# cBlocks_proto_shield.net
KiCad netlist of a schematic drawn in EAGLE
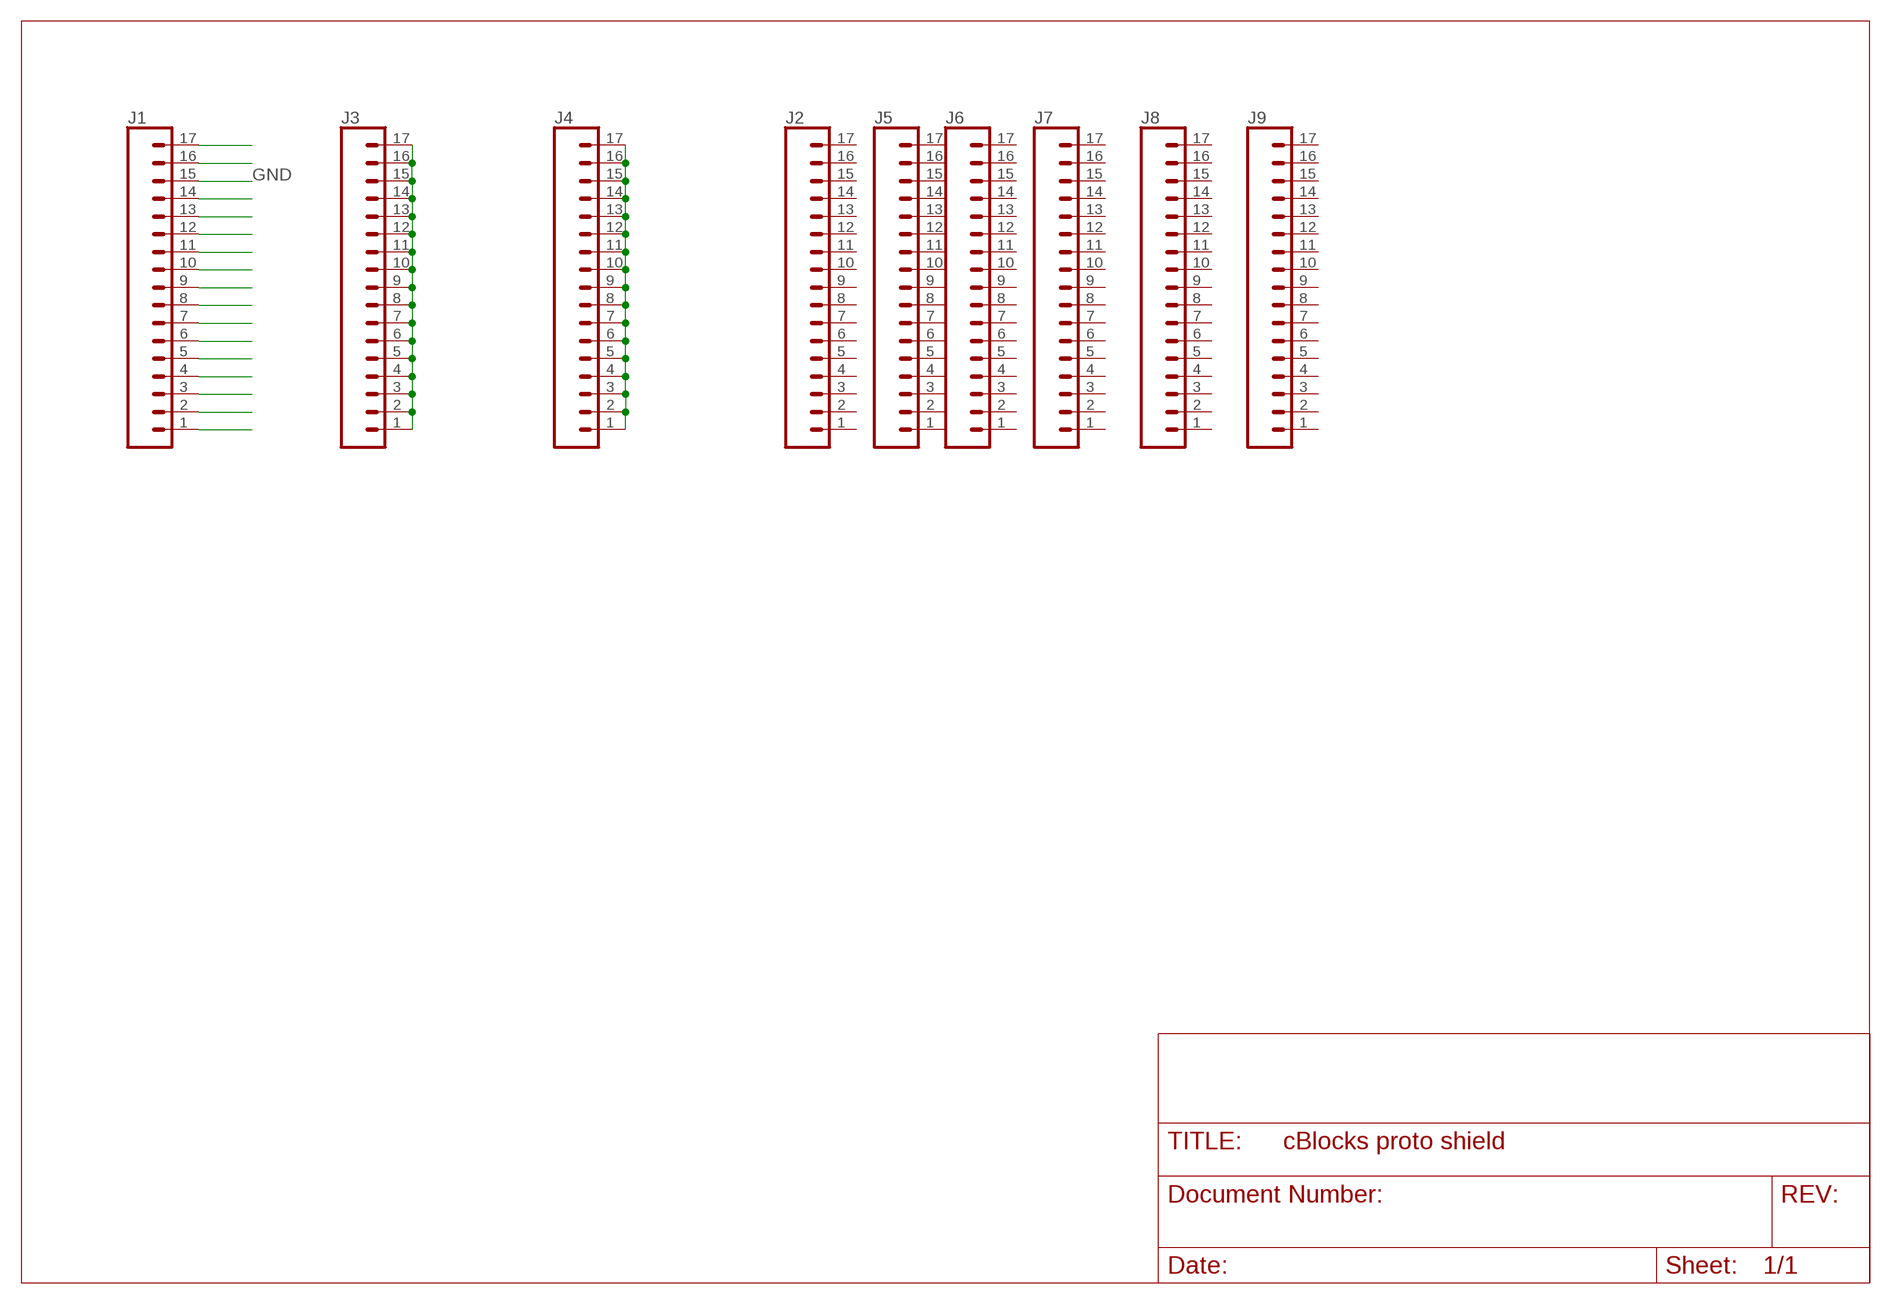
[diagram p0: schematic, sheet 1]

(export (version "E")
  (design (tool "Eeschema 10.0.6"))
  (components
    (comp (ref "J1")
      (value "CONN_17NOSILK")
      (footprint "eagle-import:1X17_NO_SILK")
      (libsource (lib "eagle-import") (part "CONN_17NOSILK"))
    )
    (comp (ref "J2")
      (value "CONN_17NOSILK")
      (footprint "eagle-import:1X17_NO_SILK")
      (libsource (lib "eagle-import") (part "CONN_17NOSILK"))
    )
    (comp (ref "J3")
      (value "CONN_17NOSILK")
      (footprint "eagle-import:1X17_NO_SILK")
      (libsource (lib "eagle-import") (part "CONN_17NOSILK"))
    )
    (comp (ref "J4")
      (value "CONN_17NOSILK")
      (footprint "eagle-import:1X17_NO_SILK")
      (libsource (lib "eagle-import") (part "CONN_17NOSILK"))
    )
    (comp (ref "J5")
      (value "CONN_17NOSILK")
      (footprint "eagle-import:1X17_NO_SILK")
      (libsource (lib "eagle-import") (part "CONN_17NOSILK"))
    )
    (comp (ref "J6")
      (value "CONN_17NOSILK")
      (footprint "eagle-import:1X17_NO_SILK")
      (libsource (lib "eagle-import") (part "CONN_17NOSILK"))
    )
    (comp (ref "J7")
      (value "CONN_17NOSILK")
      (footprint "eagle-import:1X17_NO_SILK")
      (libsource (lib "eagle-import") (part "CONN_17NOSILK"))
    )
    (comp (ref "J8")
      (value "CONN_17NOSILK")
      (footprint "eagle-import:1X17_NO_SILK")
      (libsource (lib "eagle-import") (part "CONN_17NOSILK"))
    )
    (comp (ref "J9")
      (value "CONN_17NOSILK")
      (footprint "eagle-import:1X17_NO_SILK")
      (libsource (lib "eagle-import") (part "CONN_17NOSILK"))
    )
  )
  (nets
    (net (code "1") (name "/GND") (class "Default")
      (node (ref "J1") (pin "15") (pinfunction "15_15") (pintype "passive"))
    )
    (net (code "2") (name "Net-(J3-Pad1)") (class "Default")
      (node (ref "J3") (pin "1") (pinfunction "1_1") (pintype "passive"))
      (node (ref "J3") (pin "10") (pinfunction "10_10") (pintype "passive"))
      (node (ref "J3") (pin "11") (pinfunction "11_11") (pintype "passive"))
      (node (ref "J3") (pin "12") (pinfunction "12_12") (pintype "passive"))
      (node (ref "J3") (pin "13") (pinfunction "13_13") (pintype "passive"))
      (node (ref "J3") (pin "14") (pinfunction "14_14") (pintype "passive"))
      (node (ref "J3") (pin "15") (pinfunction "15_15") (pintype "passive"))
      (node (ref "J3") (pin "16") (pinfunction "16_16") (pintype "passive"))
      (node (ref "J3") (pin "17") (pinfunction "17_17") (pintype "passive"))
      (node (ref "J3") (pin "2") (pinfunction "2_2") (pintype "passive"))
      (node (ref "J3") (pin "3") (pinfunction "3_3") (pintype "passive"))
      (node (ref "J3") (pin "4") (pinfunction "4_4") (pintype "passive"))
      (node (ref "J3") (pin "5") (pinfunction "5_5") (pintype "passive"))
      (node (ref "J3") (pin "6") (pinfunction "6_6") (pintype "passive"))
      (node (ref "J3") (pin "7") (pinfunction "7_7") (pintype "passive"))
      (node (ref "J3") (pin "8") (pinfunction "8_8") (pintype "passive"))
      (node (ref "J3") (pin "9") (pinfunction "9_9") (pintype "passive"))
    )
    (net (code "3") (name "Net-(J4-Pad1)") (class "Default")
      (node (ref "J4") (pin "1") (pinfunction "1_1") (pintype "passive"))
      (node (ref "J4") (pin "10") (pinfunction "10_10") (pintype "passive"))
      (node (ref "J4") (pin "11") (pinfunction "11_11") (pintype "passive"))
      (node (ref "J4") (pin "12") (pinfunction "12_12") (pintype "passive"))
      (node (ref "J4") (pin "13") (pinfunction "13_13") (pintype "passive"))
      (node (ref "J4") (pin "14") (pinfunction "14_14") (pintype "passive"))
      (node (ref "J4") (pin "15") (pinfunction "15_15") (pintype "passive"))
      (node (ref "J4") (pin "16") (pinfunction "16_16") (pintype "passive"))
      (node (ref "J4") (pin "17") (pinfunction "17_17") (pintype "passive"))
      (node (ref "J4") (pin "2") (pinfunction "2_2") (pintype "passive"))
      (node (ref "J4") (pin "3") (pinfunction "3_3") (pintype "passive"))
      (node (ref "J4") (pin "4") (pinfunction "4_4") (pintype "passive"))
      (node (ref "J4") (pin "5") (pinfunction "5_5") (pintype "passive"))
      (node (ref "J4") (pin "6") (pinfunction "6_6") (pintype "passive"))
      (node (ref "J4") (pin "7") (pinfunction "7_7") (pintype "passive"))
      (node (ref "J4") (pin "8") (pinfunction "8_8") (pintype "passive"))
      (node (ref "J4") (pin "9") (pinfunction "9_9") (pintype "passive"))
    )
    (net (code "4") (name "unconnected-(J1-Pad1)") (class "Default")
      (node (ref "J1") (pin "1") (pinfunction "1_1") (pintype "passive"))
    )
    (net (code "5") (name "unconnected-(J1-Pad2)") (class "Default")
      (node (ref "J1") (pin "2") (pinfunction "2_2") (pintype "passive"))
    )
    (net (code "6") (name "unconnected-(J1-Pad3)") (class "Default")
      (node (ref "J1") (pin "3") (pinfunction "3_3") (pintype "passive"))
    )
    (net (code "7") (name "unconnected-(J1-Pad4)") (class "Default")
      (node (ref "J1") (pin "4") (pinfunction "4_4") (pintype "passive"))
    )
    (net (code "8") (name "unconnected-(J1-Pad5)") (class "Default")
      (node (ref "J1") (pin "5") (pinfunction "5_5") (pintype "passive"))
    )
    (net (code "9") (name "unconnected-(J1-Pad6)") (class "Default")
      (node (ref "J1") (pin "6") (pinfunction "6_6") (pintype "passive"))
    )
    (net (code "10") (name "unconnected-(J1-Pad7)") (class "Default")
      (node (ref "J1") (pin "7") (pinfunction "7_7") (pintype "passive"))
    )
    (net (code "11") (name "unconnected-(J1-Pad8)") (class "Default")
      (node (ref "J1") (pin "8") (pinfunction "8_8") (pintype "passive"))
    )
    (net (code "12") (name "unconnected-(J1-Pad9)") (class "Default")
      (node (ref "J1") (pin "9") (pinfunction "9_9") (pintype "passive"))
    )
    (net (code "13") (name "unconnected-(J1-Pad10)") (class "Default")
      (node (ref "J1") (pin "10") (pinfunction "10_10") (pintype "passive"))
    )
    (net (code "14") (name "unconnected-(J1-Pad11)") (class "Default")
      (node (ref "J1") (pin "11") (pinfunction "11_11") (pintype "passive"))
    )
    (net (code "15") (name "unconnected-(J1-Pad12)") (class "Default")
      (node (ref "J1") (pin "12") (pinfunction "12_12") (pintype "passive"))
    )
    (net (code "16") (name "unconnected-(J1-Pad13)") (class "Default")
      (node (ref "J1") (pin "13") (pinfunction "13_13") (pintype "passive"))
    )
    (net (code "17") (name "unconnected-(J1-Pad14)") (class "Default")
      (node (ref "J1") (pin "14") (pinfunction "14_14") (pintype "passive"))
    )
    (net (code "18") (name "unconnected-(J1-Pad16)") (class "Default")
      (node (ref "J1") (pin "16") (pinfunction "16_16") (pintype "passive"))
    )
    (net (code "19") (name "unconnected-(J1-Pad17)") (class "Default")
      (node (ref "J1") (pin "17") (pinfunction "17_17") (pintype "passive"))
    )
    (net (code "20") (name "unconnected-(J2-Pad1)") (class "Default")
      (node (ref "J2") (pin "1") (pinfunction "1_1") (pintype "passive"))
    )
    (net (code "21") (name "unconnected-(J2-Pad2)") (class "Default")
      (node (ref "J2") (pin "2") (pinfunction "2_2") (pintype "passive"))
    )
    (net (code "22") (name "unconnected-(J2-Pad3)") (class "Default")
      (node (ref "J2") (pin "3") (pinfunction "3_3") (pintype "passive"))
    )
    (net (code "23") (name "unconnected-(J2-Pad4)") (class "Default")
      (node (ref "J2") (pin "4") (pinfunction "4_4") (pintype "passive"))
    )
    (net (code "24") (name "unconnected-(J2-Pad5)") (class "Default")
      (node (ref "J2") (pin "5") (pinfunction "5_5") (pintype "passive"))
    )
    (net (code "25") (name "unconnected-(J2-Pad6)") (class "Default")
      (node (ref "J2") (pin "6") (pinfunction "6_6") (pintype "passive"))
    )
    (net (code "26") (name "unconnected-(J2-Pad7)") (class "Default")
      (node (ref "J2") (pin "7") (pinfunction "7_7") (pintype "passive"))
    )
    (net (code "27") (name "unconnected-(J2-Pad8)") (class "Default")
      (node (ref "J2") (pin "8") (pinfunction "8_8") (pintype "passive"))
    )
    (net (code "28") (name "unconnected-(J2-Pad9)") (class "Default")
      (node (ref "J2") (pin "9") (pinfunction "9_9") (pintype "passive"))
    )
    (net (code "29") (name "unconnected-(J2-Pad10)") (class "Default")
      (node (ref "J2") (pin "10") (pinfunction "10_10") (pintype "passive"))
    )
    (net (code "30") (name "unconnected-(J2-Pad11)") (class "Default")
      (node (ref "J2") (pin "11") (pinfunction "11_11") (pintype "passive"))
    )
    (net (code "31") (name "unconnected-(J2-Pad12)") (class "Default")
      (node (ref "J2") (pin "12") (pinfunction "12_12") (pintype "passive"))
    )
    (net (code "32") (name "unconnected-(J2-Pad13)") (class "Default")
      (node (ref "J2") (pin "13") (pinfunction "13_13") (pintype "passive"))
    )
    (net (code "33") (name "unconnected-(J2-Pad14)") (class "Default")
      (node (ref "J2") (pin "14") (pinfunction "14_14") (pintype "passive"))
    )
    (net (code "34") (name "unconnected-(J2-Pad15)") (class "Default")
      (node (ref "J2") (pin "15") (pinfunction "15_15") (pintype "passive"))
    )
    (net (code "35") (name "unconnected-(J2-Pad16)") (class "Default")
      (node (ref "J2") (pin "16") (pinfunction "16_16") (pintype "passive"))
    )
    (net (code "36") (name "unconnected-(J2-Pad17)") (class "Default")
      (node (ref "J2") (pin "17") (pinfunction "17_17") (pintype "passive"))
    )
    (net (code "37") (name "unconnected-(J5-Pad1)") (class "Default")
      (node (ref "J5") (pin "1") (pinfunction "1_1") (pintype "passive"))
    )
    (net (code "38") (name "unconnected-(J5-Pad2)") (class "Default")
      (node (ref "J5") (pin "2") (pinfunction "2_2") (pintype "passive"))
    )
    (net (code "39") (name "unconnected-(J5-Pad3)") (class "Default")
      (node (ref "J5") (pin "3") (pinfunction "3_3") (pintype "passive"))
    )
    (net (code "40") (name "unconnected-(J5-Pad4)") (class "Default")
      (node (ref "J5") (pin "4") (pinfunction "4_4") (pintype "passive"))
    )
    (net (code "41") (name "unconnected-(J5-Pad5)") (class "Default")
      (node (ref "J5") (pin "5") (pinfunction "5_5") (pintype "passive"))
    )
    (net (code "42") (name "unconnected-(J5-Pad6)") (class "Default")
      (node (ref "J5") (pin "6") (pinfunction "6_6") (pintype "passive"))
    )
    (net (code "43") (name "unconnected-(J5-Pad7)") (class "Default")
      (node (ref "J5") (pin "7") (pinfunction "7_7") (pintype "passive"))
    )
    (net (code "44") (name "unconnected-(J5-Pad8)") (class "Default")
      (node (ref "J5") (pin "8") (pinfunction "8_8") (pintype "passive"))
    )
    (net (code "45") (name "unconnected-(J5-Pad9)") (class "Default")
      (node (ref "J5") (pin "9") (pinfunction "9_9") (pintype "passive"))
    )
    (net (code "46") (name "unconnected-(J5-Pad10)") (class "Default")
      (node (ref "J5") (pin "10") (pinfunction "10_10") (pintype "passive"))
    )
    (net (code "47") (name "unconnected-(J5-Pad11)") (class "Default")
      (node (ref "J5") (pin "11") (pinfunction "11_11") (pintype "passive"))
    )
    (net (code "48") (name "unconnected-(J5-Pad12)") (class "Default")
      (node (ref "J5") (pin "12") (pinfunction "12_12") (pintype "passive"))
    )
    (net (code "49") (name "unconnected-(J5-Pad13)") (class "Default")
      (node (ref "J5") (pin "13") (pinfunction "13_13") (pintype "passive"))
    )
    (net (code "50") (name "unconnected-(J5-Pad14)") (class "Default")
      (node (ref "J5") (pin "14") (pinfunction "14_14") (pintype "passive"))
    )
    (net (code "51") (name "unconnected-(J5-Pad15)") (class "Default")
      (node (ref "J5") (pin "15") (pinfunction "15_15") (pintype "passive"))
    )
    (net (code "52") (name "unconnected-(J5-Pad16)") (class "Default")
      (node (ref "J5") (pin "16") (pinfunction "16_16") (pintype "passive"))
    )
    (net (code "53") (name "unconnected-(J5-Pad17)") (class "Default")
      (node (ref "J5") (pin "17") (pinfunction "17_17") (pintype "passive"))
    )
    (net (code "54") (name "unconnected-(J6-Pad1)") (class "Default")
      (node (ref "J6") (pin "1") (pinfunction "1_1") (pintype "passive"))
    )
    (net (code "55") (name "unconnected-(J6-Pad2)") (class "Default")
      (node (ref "J6") (pin "2") (pinfunction "2_2") (pintype "passive"))
    )
    (net (code "56") (name "unconnected-(J6-Pad3)") (class "Default")
      (node (ref "J6") (pin "3") (pinfunction "3_3") (pintype "passive"))
    )
    (net (code "57") (name "unconnected-(J6-Pad4)") (class "Default")
      (node (ref "J6") (pin "4") (pinfunction "4_4") (pintype "passive"))
    )
    (net (code "58") (name "unconnected-(J6-Pad5)") (class "Default")
      (node (ref "J6") (pin "5") (pinfunction "5_5") (pintype "passive"))
    )
    (net (code "59") (name "unconnected-(J6-Pad6)") (class "Default")
      (node (ref "J6") (pin "6") (pinfunction "6_6") (pintype "passive"))
    )
    (net (code "60") (name "unconnected-(J6-Pad7)") (class "Default")
      (node (ref "J6") (pin "7") (pinfunction "7_7") (pintype "passive"))
    )
    (net (code "61") (name "unconnected-(J6-Pad8)") (class "Default")
      (node (ref "J6") (pin "8") (pinfunction "8_8") (pintype "passive"))
    )
    (net (code "62") (name "unconnected-(J6-Pad9)") (class "Default")
      (node (ref "J6") (pin "9") (pinfunction "9_9") (pintype "passive"))
    )
    (net (code "63") (name "unconnected-(J6-Pad10)") (class "Default")
      (node (ref "J6") (pin "10") (pinfunction "10_10") (pintype "passive"))
    )
    (net (code "64") (name "unconnected-(J6-Pad11)") (class "Default")
      (node (ref "J6") (pin "11") (pinfunction "11_11") (pintype "passive"))
    )
    (net (code "65") (name "unconnected-(J6-Pad12)") (class "Default")
      (node (ref "J6") (pin "12") (pinfunction "12_12") (pintype "passive"))
    )
    (net (code "66") (name "unconnected-(J6-Pad13)") (class "Default")
      (node (ref "J6") (pin "13") (pinfunction "13_13") (pintype "passive"))
    )
    (net (code "67") (name "unconnected-(J6-Pad14)") (class "Default")
      (node (ref "J6") (pin "14") (pinfunction "14_14") (pintype "passive"))
    )
    (net (code "68") (name "unconnected-(J6-Pad15)") (class "Default")
      (node (ref "J6") (pin "15") (pinfunction "15_15") (pintype "passive"))
    )
    (net (code "69") (name "unconnected-(J6-Pad16)") (class "Default")
      (node (ref "J6") (pin "16") (pinfunction "16_16") (pintype "passive"))
    )
    (net (code "70") (name "unconnected-(J6-Pad17)") (class "Default")
      (node (ref "J6") (pin "17") (pinfunction "17_17") (pintype "passive"))
    )
    (net (code "71") (name "unconnected-(J7-Pad1)") (class "Default")
      (node (ref "J7") (pin "1") (pinfunction "1_1") (pintype "passive"))
    )
    (net (code "72") (name "unconnected-(J7-Pad2)") (class "Default")
      (node (ref "J7") (pin "2") (pinfunction "2_2") (pintype "passive"))
    )
    (net (code "73") (name "unconnected-(J7-Pad3)") (class "Default")
      (node (ref "J7") (pin "3") (pinfunction "3_3") (pintype "passive"))
    )
    (net (code "74") (name "unconnected-(J7-Pad4)") (class "Default")
      (node (ref "J7") (pin "4") (pinfunction "4_4") (pintype "passive"))
    )
    (net (code "75") (name "unconnected-(J7-Pad5)") (class "Default")
      (node (ref "J7") (pin "5") (pinfunction "5_5") (pintype "passive"))
    )
    (net (code "76") (name "unconnected-(J7-Pad6)") (class "Default")
      (node (ref "J7") (pin "6") (pinfunction "6_6") (pintype "passive"))
    )
    (net (code "77") (name "unconnected-(J7-Pad7)") (class "Default")
      (node (ref "J7") (pin "7") (pinfunction "7_7") (pintype "passive"))
    )
    (net (code "78") (name "unconnected-(J7-Pad8)") (class "Default")
      (node (ref "J7") (pin "8") (pinfunction "8_8") (pintype "passive"))
    )
    (net (code "79") (name "unconnected-(J7-Pad9)") (class "Default")
      (node (ref "J7") (pin "9") (pinfunction "9_9") (pintype "passive"))
    )
    (net (code "80") (name "unconnected-(J7-Pad10)") (class "Default")
      (node (ref "J7") (pin "10") (pinfunction "10_10") (pintype "passive"))
    )
    (net (code "81") (name "unconnected-(J7-Pad11)") (class "Default")
      (node (ref "J7") (pin "11") (pinfunction "11_11") (pintype "passive"))
    )
    (net (code "82") (name "unconnected-(J7-Pad12)") (class "Default")
      (node (ref "J7") (pin "12") (pinfunction "12_12") (pintype "passive"))
    )
    (net (code "83") (name "unconnected-(J7-Pad13)") (class "Default")
      (node (ref "J7") (pin "13") (pinfunction "13_13") (pintype "passive"))
    )
    (net (code "84") (name "unconnected-(J7-Pad14)") (class "Default")
      (node (ref "J7") (pin "14") (pinfunction "14_14") (pintype "passive"))
    )
    (net (code "85") (name "unconnected-(J7-Pad15)") (class "Default")
      (node (ref "J7") (pin "15") (pinfunction "15_15") (pintype "passive"))
    )
    (net (code "86") (name "unconnected-(J7-Pad16)") (class "Default")
      (node (ref "J7") (pin "16") (pinfunction "16_16") (pintype "passive"))
    )
    (net (code "87") (name "unconnected-(J7-Pad17)") (class "Default")
      (node (ref "J7") (pin "17") (pinfunction "17_17") (pintype "passive"))
    )
    (net (code "88") (name "unconnected-(J8-Pad1)") (class "Default")
      (node (ref "J8") (pin "1") (pinfunction "1_1") (pintype "passive"))
    )
    (net (code "89") (name "unconnected-(J8-Pad2)") (class "Default")
      (node (ref "J8") (pin "2") (pinfunction "2_2") (pintype "passive"))
    )
    (net (code "90") (name "unconnected-(J8-Pad3)") (class "Default")
      (node (ref "J8") (pin "3") (pinfunction "3_3") (pintype "passive"))
    )
    (net (code "91") (name "unconnected-(J8-Pad4)") (class "Default")
      (node (ref "J8") (pin "4") (pinfunction "4_4") (pintype "passive"))
    )
    (net (code "92") (name "unconnected-(J8-Pad5)") (class "Default")
      (node (ref "J8") (pin "5") (pinfunction "5_5") (pintype "passive"))
    )
    (net (code "93") (name "unconnected-(J8-Pad6)") (class "Default")
      (node (ref "J8") (pin "6") (pinfunction "6_6") (pintype "passive"))
    )
    (net (code "94") (name "unconnected-(J8-Pad7)") (class "Default")
      (node (ref "J8") (pin "7") (pinfunction "7_7") (pintype "passive"))
    )
    (net (code "95") (name "unconnected-(J8-Pad8)") (class "Default")
      (node (ref "J8") (pin "8") (pinfunction "8_8") (pintype "passive"))
    )
    (net (code "96") (name "unconnected-(J8-Pad9)") (class "Default")
      (node (ref "J8") (pin "9") (pinfunction "9_9") (pintype "passive"))
    )
    (net (code "97") (name "unconnected-(J8-Pad10)") (class "Default")
      (node (ref "J8") (pin "10") (pinfunction "10_10") (pintype "passive"))
    )
    (net (code "98") (name "unconnected-(J8-Pad11)") (class "Default")
      (node (ref "J8") (pin "11") (pinfunction "11_11") (pintype "passive"))
    )
    (net (code "99") (name "unconnected-(J8-Pad12)") (class "Default")
      (node (ref "J8") (pin "12") (pinfunction "12_12") (pintype "passive"))
    )
    (net (code "100") (name "unconnected-(J8-Pad13)") (class "Default")
      (node (ref "J8") (pin "13") (pinfunction "13_13") (pintype "passive"))
    )
    (net (code "101") (name "unconnected-(J8-Pad14)") (class "Default")
      (node (ref "J8") (pin "14") (pinfunction "14_14") (pintype "passive"))
    )
    (net (code "102") (name "unconnected-(J8-Pad15)") (class "Default")
      (node (ref "J8") (pin "15") (pinfunction "15_15") (pintype "passive"))
    )
    (net (code "103") (name "unconnected-(J8-Pad16)") (class "Default")
      (node (ref "J8") (pin "16") (pinfunction "16_16") (pintype "passive"))
    )
    (net (code "104") (name "unconnected-(J8-Pad17)") (class "Default")
      (node (ref "J8") (pin "17") (pinfunction "17_17") (pintype "passive"))
    )
    (net (code "105") (name "unconnected-(J9-Pad1)") (class "Default")
      (node (ref "J9") (pin "1") (pinfunction "1_1") (pintype "passive"))
    )
    (net (code "106") (name "unconnected-(J9-Pad2)") (class "Default")
      (node (ref "J9") (pin "2") (pinfunction "2_2") (pintype "passive"))
    )
    (net (code "107") (name "unconnected-(J9-Pad3)") (class "Default")
      (node (ref "J9") (pin "3") (pinfunction "3_3") (pintype "passive"))
    )
    (net (code "108") (name "unconnected-(J9-Pad4)") (class "Default")
      (node (ref "J9") (pin "4") (pinfunction "4_4") (pintype "passive"))
    )
    (net (code "109") (name "unconnected-(J9-Pad5)") (class "Default")
      (node (ref "J9") (pin "5") (pinfunction "5_5") (pintype "passive"))
    )
    (net (code "110") (name "unconnected-(J9-Pad6)") (class "Default")
      (node (ref "J9") (pin "6") (pinfunction "6_6") (pintype "passive"))
    )
    (net (code "111") (name "unconnected-(J9-Pad7)") (class "Default")
      (node (ref "J9") (pin "7") (pinfunction "7_7") (pintype "passive"))
    )
    (net (code "112") (name "unconnected-(J9-Pad8)") (class "Default")
      (node (ref "J9") (pin "8") (pinfunction "8_8") (pintype "passive"))
    )
    (net (code "113") (name "unconnected-(J9-Pad9)") (class "Default")
      (node (ref "J9") (pin "9") (pinfunction "9_9") (pintype "passive"))
    )
    (net (code "114") (name "unconnected-(J9-Pad10)") (class "Default")
      (node (ref "J9") (pin "10") (pinfunction "10_10") (pintype "passive"))
    )
    (net (code "115") (name "unconnected-(J9-Pad11)") (class "Default")
      (node (ref "J9") (pin "11") (pinfunction "11_11") (pintype "passive"))
    )
    (net (code "116") (name "unconnected-(J9-Pad12)") (class "Default")
      (node (ref "J9") (pin "12") (pinfunction "12_12") (pintype "passive"))
    )
    (net (code "117") (name "unconnected-(J9-Pad13)") (class "Default")
      (node (ref "J9") (pin "13") (pinfunction "13_13") (pintype "passive"))
    )
    (net (code "118") (name "unconnected-(J9-Pad14)") (class "Default")
      (node (ref "J9") (pin "14") (pinfunction "14_14") (pintype "passive"))
    )
    (net (code "119") (name "unconnected-(J9-Pad15)") (class "Default")
      (node (ref "J9") (pin "15") (pinfunction "15_15") (pintype "passive"))
    )
    (net (code "120") (name "unconnected-(J9-Pad16)") (class "Default")
      (node (ref "J9") (pin "16") (pinfunction "16_16") (pintype "passive"))
    )
    (net (code "121") (name "unconnected-(J9-Pad17)") (class "Default")
      (node (ref "J9") (pin "17") (pinfunction "17_17") (pintype "passive"))
    )
  )
)
